# DOOM_SAO.net
KiCad netlist of a schematic drawn in EAGLE
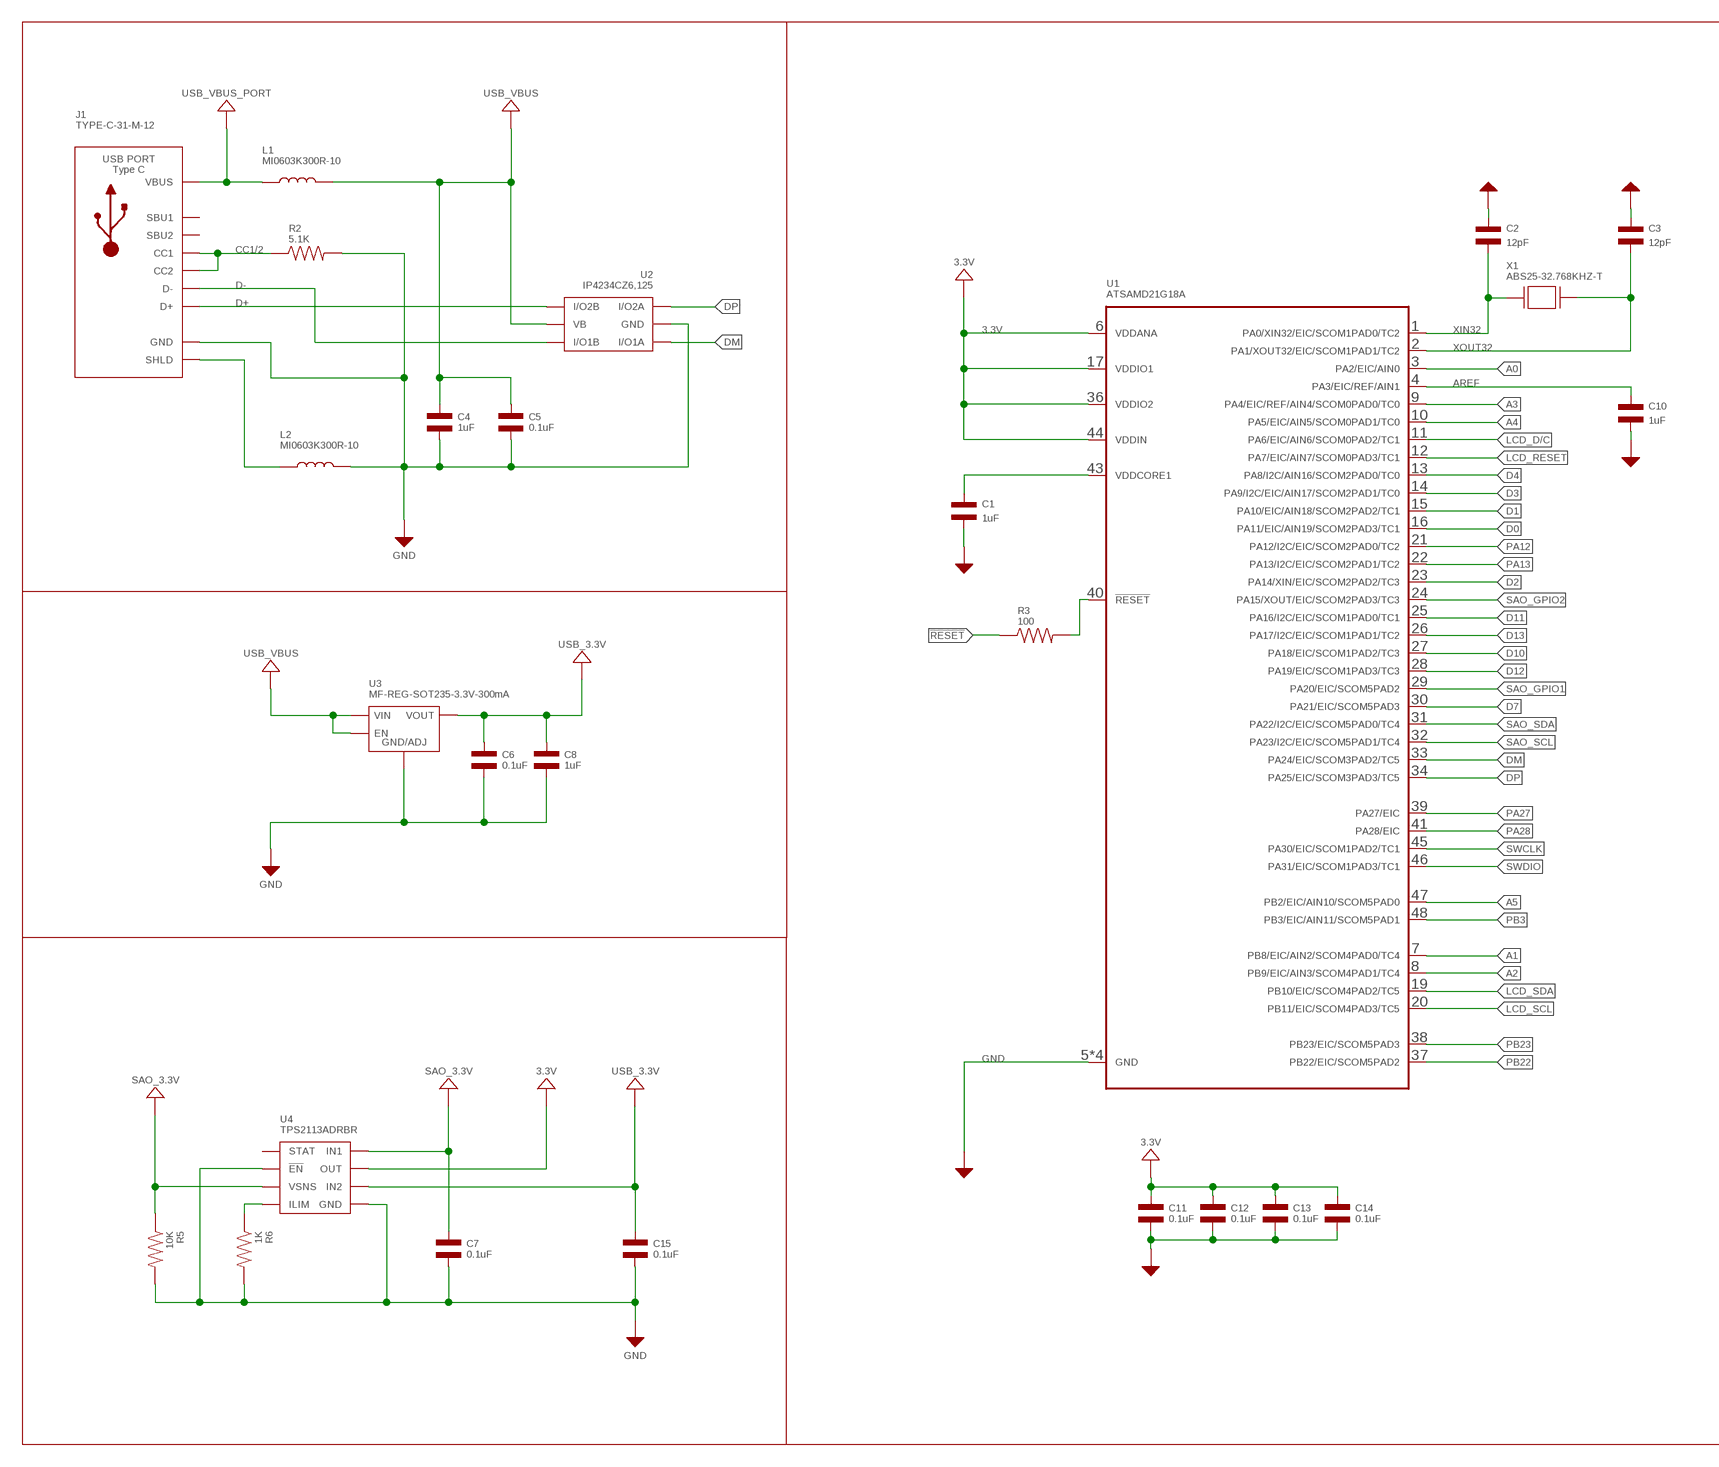
[diagram p0: schematic, sheet 1, part 1 of 2]
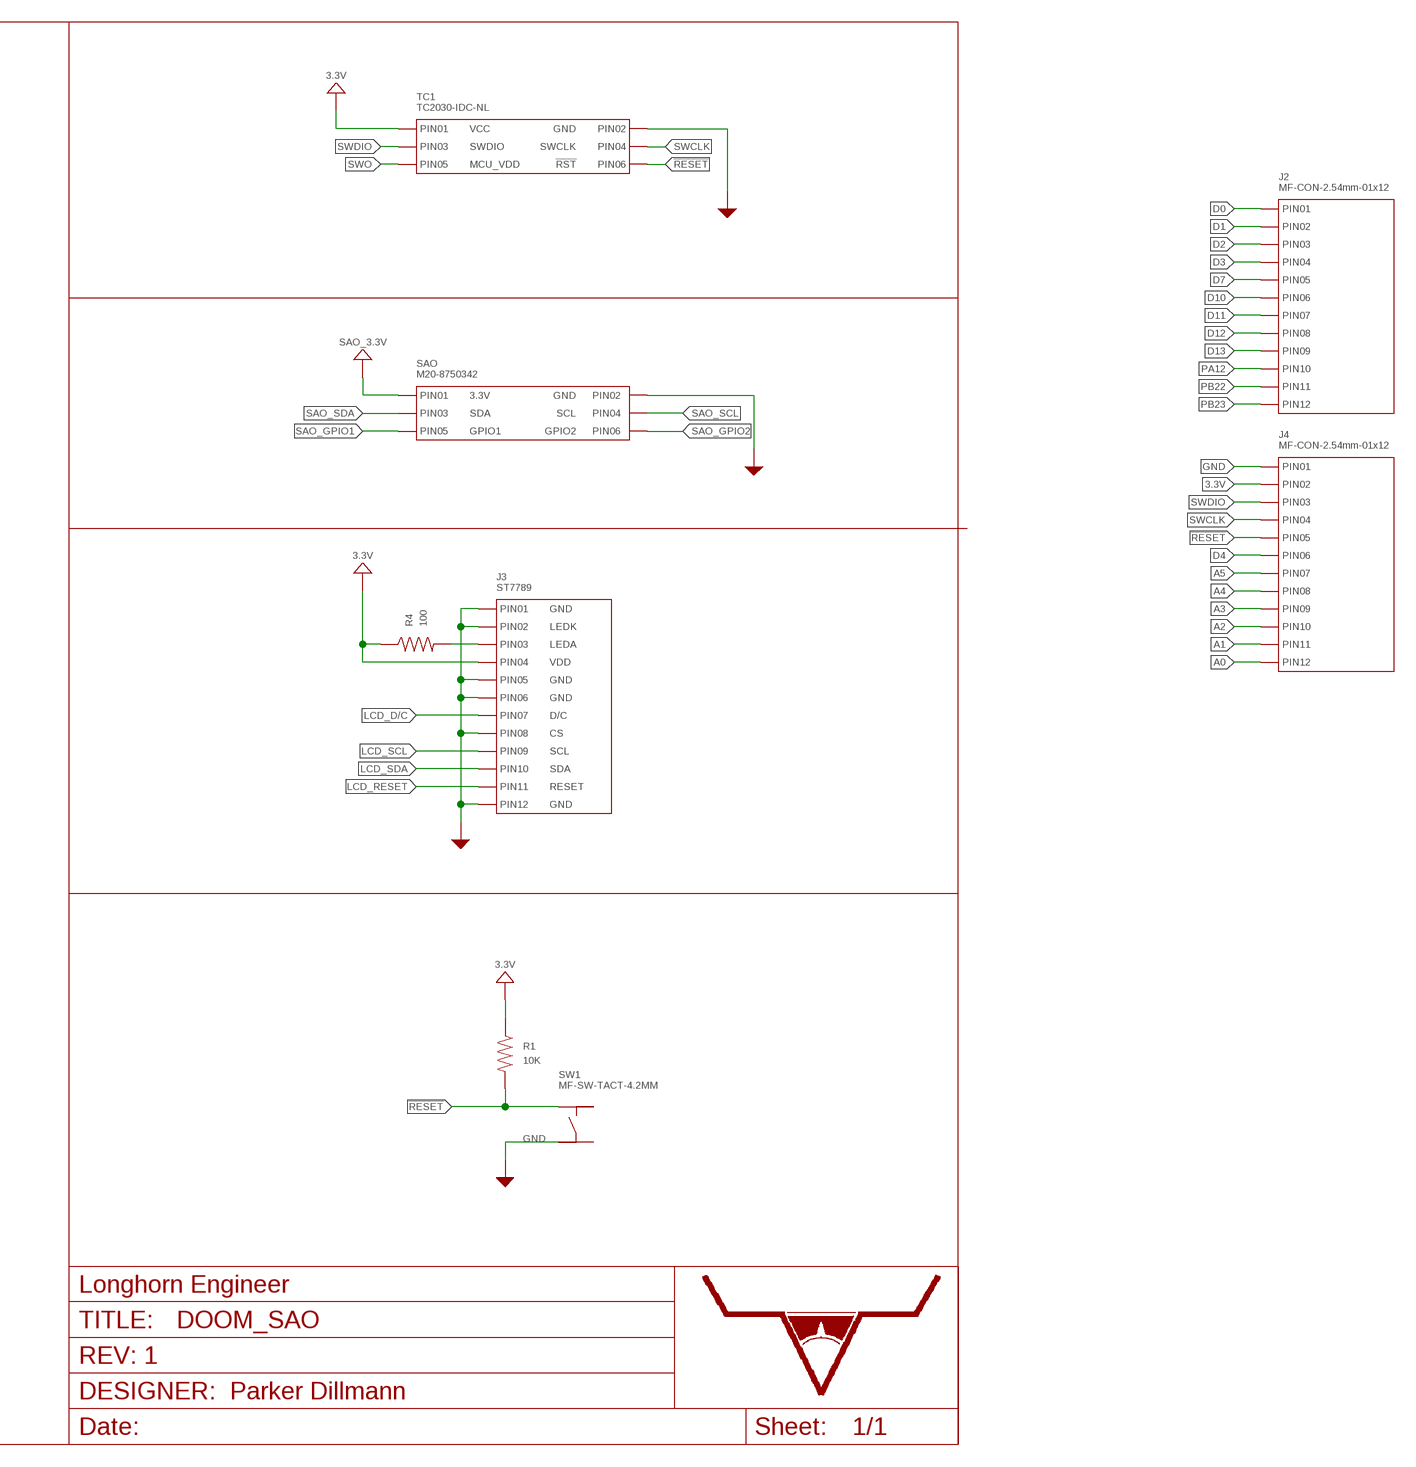
[diagram p1: schematic, sheet 1, part 2 of 2]

(export (version "E")
  (design (tool "Eeschema 10.0.6"))
  (components
    (comp (ref "C1")
      (value "1uF")
      (footprint "eagle-import:C0402")
      (fields (field (name "MPN") "MF-CAP-0402-1uF"))
      (libsource (lib "eagle-import") (part "CAPACITOR_NP_0402"))
    )
    (comp (ref "C2")
      (value "12pF")
      (footprint "eagle-import:C0402")
      (fields (field (name "MPN") "CC0402JRNPO9BN120"))
      (libsource (lib "eagle-import") (part "CAPACITOR_NP_0402"))
    )
    (comp (ref "C3")
      (value "12pF")
      (footprint "eagle-import:C0402")
      (fields (field (name "MPN") "CC0402JRNPO9BN120"))
      (libsource (lib "eagle-import") (part "CAPACITOR_NP_0402"))
    )
    (comp (ref "C4")
      (value "1uF")
      (footprint "eagle-import:C0402")
      (fields (field (name "MPN") "MF-CAP-0402-1uF"))
      (libsource (lib "eagle-import") (part "CAPACITOR_NP_0402"))
    )
    (comp (ref "C5")
      (value "0.1uF")
      (footprint "eagle-import:C0402")
      (fields (field (name "MPN") "MF-CAP-0402-0.1uF"))
      (libsource (lib "eagle-import") (part "CAPACITOR_NP_0402"))
    )
    (comp (ref "C6")
      (value "0.1uF")
      (footprint "eagle-import:C0402")
      (fields (field (name "MPN") "MF-CAP-0402-0.1uF"))
      (libsource (lib "eagle-import") (part "CAPACITOR_NP_0402"))
    )
    (comp (ref "C7")
      (value "0.1uF")
      (footprint "eagle-import:C0402")
      (fields (field (name "MPN") "MF-CAP-0402-0.1uF"))
      (libsource (lib "eagle-import") (part "CAPACITOR_NP_0402"))
    )
    (comp (ref "C8")
      (value "1uF")
      (footprint "eagle-import:C0402")
      (fields (field (name "MPN") "MF-CAP-0402-1uF"))
      (libsource (lib "eagle-import") (part "CAPACITOR_NP_0402"))
    )
    (comp (ref "C10")
      (value "1uF")
      (footprint "eagle-import:C0402")
      (fields (field (name "MPN") "MF-CAP-0402-1uF"))
      (libsource (lib "eagle-import") (part "CAPACITOR_NP_0402"))
    )
    (comp (ref "C11")
      (value "0.1uF")
      (footprint "eagle-import:C0402")
      (fields (field (name "MPN") "MF-CAP-0402-0.1uF"))
      (libsource (lib "eagle-import") (part "CAPACITOR_NP_0402"))
    )
    (comp (ref "C12")
      (value "0.1uF")
      (footprint "eagle-import:C0402")
      (fields (field (name "MPN") "MF-CAP-0402-0.1uF"))
      (libsource (lib "eagle-import") (part "CAPACITOR_NP_0402"))
    )
    (comp (ref "C13")
      (value "0.1uF")
      (footprint "eagle-import:C0402")
      (fields (field (name "MPN") "MF-CAP-0402-0.1uF"))
      (libsource (lib "eagle-import") (part "CAPACITOR_NP_0402"))
    )
    (comp (ref "C14")
      (value "0.1uF")
      (footprint "eagle-import:C0402")
      (fields (field (name "MPN") "MF-CAP-0402-0.1uF"))
      (libsource (lib "eagle-import") (part "CAPACITOR_NP_0402"))
    )
    (comp (ref "C15")
      (value "0.1uF")
      (footprint "eagle-import:C0402")
      (fields (field (name "MPN") "MF-CAP-0402-0.1uF"))
      (libsource (lib "eagle-import") (part "CAPACITOR_NP_0402"))
    )
    (comp (ref "J1")
      (value "TYPE-C-31-M-12")
      (footprint "eagle-import:TYPE-C-31-M-12")
      (libsource (lib "eagle-import") (part "USB_TYPE-C_MINIMAL"))
    )
    (comp (ref "J2")
      (value "MF-CON-2.54mm-01x12")
      (footprint "eagle-import:PTH_2.54MM_01X12")
      (fields (field (name "HOUSEPART") "YES"))
      (libsource (lib "eagle-import") (part "CON_01X12_PTH_2.54MM"))
    )
    (comp (ref "J3")
      (value "ST7789")
      (footprint "eagle-import:ST7789_CONNECTOR")
      (fields
        (field (name "LABEL01") "GND")
        (field (name "LABEL02") "LEDK")
        (field (name "LABEL03") "LEDA")
        (field (name "LABEL04") "VDD")
        (field (name "LABEL05") "GND")
        (field (name "LABEL06") "GND")
        (field (name "LABEL07") "D/C")
        (field (name "LABEL08") "CS")
        (field (name "LABEL09") "SCL")
        (field (name "LABEL10") "SDA")
        (field (name "LABEL11") "RESET")
        (field (name "LABEL12") "GND")
      )
      (libsource (lib "eagle-import") (part "CON_01X12_ST7789_CONNECTOR"))
    )
    (comp (ref "J4")
      (value "MF-CON-2.54mm-01x12")
      (footprint "eagle-import:PTH_2.54MM_01X12")
      (fields (field (name "HOUSEPART") "YES"))
      (libsource (lib "eagle-import") (part "CON_01X12_PTH_2.54MM"))
    )
    (comp (ref "L1")
      (value "MI0603K300R-10")
      (footprint "eagle-import:L0603")
      (fields (field (name "MPN") "MI0603K300R-10"))
      (libsource (lib "eagle-import") (part "INDUCTOR_0603"))
    )
    (comp (ref "L2")
      (value "MI0603K300R-10")
      (footprint "eagle-import:L0603")
      (fields (field (name "MPN") "MI0603K300R-10"))
      (libsource (lib "eagle-import") (part "INDUCTOR_0603"))
    )
    (comp (ref "R1")
      (value "10K")
      (footprint "eagle-import:R0402")
      (fields (field (name "MPN") "MF-RES-0402-10K"))
      (libsource (lib "eagle-import") (part "RESISTOR_0402"))
    )
    (comp (ref "R2")
      (value "5.1K")
      (footprint "eagle-import:R0402")
      (fields (field (name "MPN") "ERJ-2RHD5101X"))
      (libsource (lib "eagle-import") (part "RESISTOR_0402"))
    )
    (comp (ref "R3")
      (value "100")
      (footprint "eagle-import:R0402")
      (fields (field (name "MPN") "MF-RES-0402-100"))
      (libsource (lib "eagle-import") (part "RESISTOR_0402"))
    )
    (comp (ref "R4")
      (value "100")
      (footprint "eagle-import:R0402")
      (fields (field (name "MPN") "MF-RES-0402-100"))
      (libsource (lib "eagle-import") (part "RESISTOR_0402"))
    )
    (comp (ref "R5")
      (value "10K")
      (footprint "eagle-import:R0402")
      (fields (field (name "MPN") "MF-RES-0402-10K"))
      (libsource (lib "eagle-import") (part "RESISTOR_0402"))
    )
    (comp (ref "R6")
      (value "1K")
      (footprint "eagle-import:R0402")
      (fields (field (name "MPN") "MF-RES-0402-1K"))
      (libsource (lib "eagle-import") (part "RESISTOR_0402"))
    )
    (comp (ref "SAO")
      (value "M20-8750342")
      (footprint "eagle-import:M20-8750342")
      (fields
        (field (name "LABEL01") "3.3V")
        (field (name "LABEL02") "GND")
        (field (name "LABEL03") "SDA")
        (field (name "LABEL04") "SCL")
        (field (name "LABEL05") "GPIO1")
        (field (name "LABEL06") "GPIO2")
        (field (name "MPN") "M20-8750342 ")
        (field (name "POPULATE") "1")
      )
      (libsource (lib "eagle-import") (part "CON_02X03_M20-8750342"))
    )
    (comp (ref "SW1")
      (value "MF-SW-TACT-4.2MM")
      (footprint "eagle-import:TACT4.2MM")
      (fields (field (name "HOUSEPART") "YES"))
      (libsource (lib "eagle-import") (part "TACT_4.2MM"))
    )
    (comp (ref "TC1")
      (value "TC2030-IDC-NL")
      (footprint "eagle-import:TC2030-IDC-NL")
      (fields
        (field (name "HOUSEPART") "NO")
        (field (name "LABEL01") "VCC")
        (field (name "LABEL02") "GND")
        (field (name "LABEL03") "SWDIO")
        (field (name "LABEL04") "SWCLK")
        (field (name "LABEL05") "MCU_VDD")
        (field (name "LABEL06") "!RST")
      )
      (libsource (lib "eagle-import") (part "CON_02X03_TC2030-IDC-NL_SWD2TC"))
    )
    (comp (ref "U$8")
      (value "LHE_FRAME")
      (footprint "eagle-import:LHE_FRAME")
      (fields (field (name "DNAME") "Parker Dillmann") (field (name "REVNUM") "REV: 1"))
      (libsource (lib "eagle-import") (part "LHE_FRAME"))
    )
    (comp (ref "U1")
      (value "ATSAMD21G18A")
      (footprint "eagle-import:ATSAMD21G18A_TQFP-48")
      (fields (field (name "MPN") "ATSAMD21G18A-AU"))
      (libsource (lib "eagle-import") (part "ATSAMD21G18A-AU"))
    )
    (comp (ref "U2")
      (value "IP4234CZ6,125")
      (footprint "eagle-import:IP4234CZ6_SOT-457-6")
      (libsource (lib "eagle-import") (part "IP4234CZ6"))
    )
    (comp (ref "U3")
      (value "MF-REG-SOT235-3.3V-300mA")
      (footprint "eagle-import:SOT-23-5")
      (fields (field (name "HOUSEPART") "YES"))
      (libsource (lib "eagle-import") (part "TLV70233PDBVR"))
    )
    (comp (ref "U4")
      (value "TPS2113ADRBR")
      (footprint "eagle-import:TPS211X_SON-8")
      (libsource (lib "eagle-import") (part "TPS211(2/3)ADR"))
    )
    (comp (ref "X1")
      (value "ABS25-32.768KHZ-T")
      (footprint "eagle-import:ABS25_SERIES")
      (fields (field (name "HOUSEPART") "NO") (field (name "MPN") "ABS25-32.768KHZ-T "))
      (libsource (lib "eagle-import") (part "CYRSTAL_ABS25"))
    )
  )
  (nets
    (net (code "1") (name "/AREF") (class "Default")
      (node (ref "C10") (pin "P$1") (pinfunction "P$1_P$1") (pintype "passive"))
      (node (ref "U1") (pin "4") (pinfunction "PA3/EIC/REF/AIN1_4") (pintype "bidirectional"))
    )
    (net (code "2") (name "/CC1{slash}2") (class "Default")
      (node (ref "J1") (pin "A5") (pinfunction "CC1_A5") (pintype "bidirectional"))
      (node (ref "J1") (pin "B5") (pinfunction "CC2_B5") (pintype "bidirectional"))
      (node (ref "R2") (pin "P$1") (pinfunction "P$1_P$1") (pintype "passive"))
    )
    (net (code "3") (name "/D+") (class "Default")
      (node (ref "J1") (pin "A6") (pinfunction "D+_A6") (pintype "bidirectional"))
      (node (ref "J1") (pin "B6") (pinfunction "D+_B6") (pintype "bidirectional"))
      (node (ref "U2") (pin "4") (pinfunction "I/O2B_4") (pintype "bidirectional"))
    )
    (net (code "4") (name "/D-") (class "Default")
      (node (ref "J1") (pin "A7") (pinfunction "D-_A7") (pintype "bidirectional"))
      (node (ref "J1") (pin "B7") (pinfunction "D-_B7") (pintype "bidirectional"))
      (node (ref "U2") (pin "3") (pinfunction "I/O1B_3") (pintype "bidirectional"))
    )
    (net (code "5") (name "/XIN32") (class "Default")
      (node (ref "C2") (pin "P$2") (pinfunction "P$2_P$2") (pintype "passive"))
      (node (ref "U1") (pin "1") (pinfunction "PA0/XIN32/EIC/SCOM1PAD0/TC2_1") (pintype "bidirectional"))
      (node (ref "X1") (pin "1") (pinfunction "X0_1") (pintype "bidirectional"))
    )
    (net (code "6") (name "/XOUT32") (class "Default")
      (node (ref "C3") (pin "P$2") (pinfunction "P$2_P$2") (pintype "passive"))
      (node (ref "U1") (pin "2") (pinfunction "PA1/XOUT32/EIC/SCOM1PAD1/TC2_2") (pintype "bidirectional"))
      (node (ref "X1") (pin "4") (pinfunction "X1_4") (pintype "bidirectional"))
    )
    (net (code "7") (name "/~{RESET}") (class "Default")
      (node (ref "J4") (pin "P$5") (pinfunction "PIN5_P$5") (pintype "bidirectional"))
      (node (ref "R1") (pin "P$2") (pinfunction "P$2_P$2") (pintype "passive"))
      (node (ref "R3") (pin "P$1") (pinfunction "P$1_P$1") (pintype "passive"))
      (node (ref "SW1") (pin "P$1") (pinfunction "P$1_P$1") (pintype "bidirectional"))
      (node (ref "TC1") (pin "P$6") (pinfunction "PIN6_P$6") (pintype "bidirectional"))
    )
    (net (code "8") (name "3.3V") (class "Default")
      (node (ref "C11") (pin "P$1") (pinfunction "P$1_P$1") (pintype "passive"))
      (node (ref "C12") (pin "P$1") (pinfunction "P$1_P$1") (pintype "passive"))
      (node (ref "C13") (pin "P$1") (pinfunction "P$1_P$1") (pintype "passive"))
      (node (ref "C14") (pin "P$1") (pinfunction "P$1_P$1") (pintype "passive"))
      (node (ref "J3") (pin "P$4") (pinfunction "4_P$4") (pintype "bidirectional"))
      (node (ref "J4") (pin "P$2") (pinfunction "PIN2_P$2") (pintype "bidirectional"))
      (node (ref "R1") (pin "P$1") (pinfunction "P$1_P$1") (pintype "passive"))
      (node (ref "R4") (pin "P$1") (pinfunction "P$1_P$1") (pintype "passive"))
      (node (ref "TC1") (pin "P$1") (pinfunction "PIN1_P$1") (pintype "bidirectional"))
      (node (ref "U1") (pin "17") (pinfunction "VDDIO1_17") (pintype "bidirectional"))
      (node (ref "U1") (pin "36") (pinfunction "VDDIO2_36") (pintype "bidirectional"))
      (node (ref "U1") (pin "44") (pinfunction "VDDIN_44") (pintype "bidirectional"))
      (node (ref "U1") (pin "6") (pinfunction "VDDANA_6") (pintype "bidirectional"))
      (node (ref "U4") (pin "7") (pinfunction "OUT_7") (pintype "bidirectional"))
    )
    (net (code "9") (name "A0") (class "Default")
      (node (ref "J4") (pin "P$12") (pinfunction "PIN12_P$12") (pintype "bidirectional"))
      (node (ref "U1") (pin "3") (pinfunction "PA2/EIC/AIN0_3") (pintype "bidirectional"))
    )
    (net (code "10") (name "A1") (class "Default")
      (node (ref "J4") (pin "P$11") (pinfunction "PIN11_P$11") (pintype "bidirectional"))
      (node (ref "U1") (pin "7") (pinfunction "PB8/EIC/AIN2/SCOM4PAD0/TC4_7") (pintype "bidirectional"))
    )
    (net (code "11") (name "A2") (class "Default")
      (node (ref "J4") (pin "P$10") (pinfunction "PIN10_P$10") (pintype "bidirectional"))
      (node (ref "U1") (pin "8") (pinfunction "PB9/EIC/AIN3/SCOM4PAD1/TC4_8") (pintype "bidirectional"))
    )
    (net (code "12") (name "A3") (class "Default")
      (node (ref "J4") (pin "P$9") (pinfunction "PIN9_P$9") (pintype "bidirectional"))
      (node (ref "U1") (pin "9") (pinfunction "PA4/EIC/REF/AIN4/SCOM0PAD0/TC0_9") (pintype "bidirectional"))
    )
    (net (code "13") (name "A4") (class "Default")
      (node (ref "J4") (pin "P$8") (pinfunction "PIN8_P$8") (pintype "bidirectional"))
      (node (ref "U1") (pin "10") (pinfunction "PA5/EIC/AIN5/SCOM0PAD1/TC0_10") (pintype "bidirectional"))
    )
    (net (code "14") (name "A5") (class "Default")
      (node (ref "J4") (pin "P$7") (pinfunction "PIN7_P$7") (pintype "bidirectional"))
      (node (ref "U1") (pin "47") (pinfunction "PB2/EIC/AIN10/SCOM5PAD0_47") (pintype "bidirectional"))
    )
    (net (code "15") (name "D0") (class "Default")
      (node (ref "J2") (pin "P$1") (pinfunction "PIN1_P$1") (pintype "bidirectional"))
      (node (ref "U1") (pin "16") (pinfunction "PA11/EIC/AIN19/SCOM2PAD3/TC1_16") (pintype "bidirectional"))
    )
    (net (code "16") (name "D1") (class "Default")
      (node (ref "J2") (pin "P$2") (pinfunction "PIN2_P$2") (pintype "bidirectional"))
      (node (ref "U1") (pin "15") (pinfunction "PA10/EIC/AIN18/SCOM2PAD2/TC1_15") (pintype "bidirectional"))
    )
    (net (code "17") (name "D2") (class "Default")
      (node (ref "J2") (pin "P$3") (pinfunction "PIN3_P$3") (pintype "bidirectional"))
      (node (ref "U1") (pin "23") (pinfunction "PA14/XIN/EIC/SCOM2PAD2/TC3_23") (pintype "bidirectional"))
    )
    (net (code "18") (name "D3") (class "Default")
      (node (ref "J2") (pin "P$4") (pinfunction "PIN4_P$4") (pintype "bidirectional"))
      (node (ref "U1") (pin "14") (pinfunction "PA9/I2C/EIC/AIN17/SCOM2PAD1/TC0_14") (pintype "bidirectional"))
    )
    (net (code "19") (name "D4") (class "Default")
      (node (ref "J4") (pin "P$6") (pinfunction "PIN6_P$6") (pintype "bidirectional"))
      (node (ref "U1") (pin "13") (pinfunction "PA8/I2C/AIN16/SCOM2PAD0/TC0_13") (pintype "bidirectional"))
    )
    (net (code "20") (name "D7") (class "Default")
      (node (ref "J2") (pin "P$5") (pinfunction "PIN5_P$5") (pintype "bidirectional"))
      (node (ref "U1") (pin "30") (pinfunction "PA21/EIC/SCOM5PAD3_30") (pintype "bidirectional"))
    )
    (net (code "21") (name "D10") (class "Default")
      (node (ref "J2") (pin "P$6") (pinfunction "PIN6_P$6") (pintype "bidirectional"))
      (node (ref "U1") (pin "27") (pinfunction "PA18/EIC/SCOM1PAD2/TC3_27") (pintype "bidirectional"))
    )
    (net (code "22") (name "D11") (class "Default")
      (node (ref "J2") (pin "P$7") (pinfunction "PIN7_P$7") (pintype "bidirectional"))
      (node (ref "U1") (pin "25") (pinfunction "PA16/I2C/EIC/SCOM1PAD0/TC1_25") (pintype "bidirectional"))
    )
    (net (code "23") (name "D12") (class "Default")
      (node (ref "J2") (pin "P$8") (pinfunction "PIN8_P$8") (pintype "bidirectional"))
      (node (ref "U1") (pin "28") (pinfunction "PA19/EIC/SCOM1PAD3/TC3_28") (pintype "bidirectional"))
    )
    (net (code "24") (name "D13") (class "Default")
      (node (ref "J2") (pin "P$9") (pinfunction "PIN9_P$9") (pintype "bidirectional"))
      (node (ref "U1") (pin "26") (pinfunction "PA17/I2C/EIC/SCOM1PAD1/TC2_26") (pintype "bidirectional"))
    )
    (net (code "25") (name "DM") (class "Default")
      (node (ref "U1") (pin "33") (pinfunction "PA24/EIC/SCOM3PAD2/TC5_33") (pintype "bidirectional"))
      (node (ref "U2") (pin "1") (pinfunction "I/O1A_1") (pintype "bidirectional"))
    )
    (net (code "26") (name "DP") (class "Default")
      (node (ref "U1") (pin "34") (pinfunction "PA25/EIC/SCOM3PAD3/TC5_34") (pintype "bidirectional"))
      (node (ref "U2") (pin "6") (pinfunction "I/O2A_6") (pintype "bidirectional"))
    )
    (net (code "27") (name "GND") (class "Default")
      (node (ref "C1") (pin "P$2") (pinfunction "P$2_P$2") (pintype "passive"))
      (node (ref "C10") (pin "P$2") (pinfunction "P$2_P$2") (pintype "passive"))
      (node (ref "C11") (pin "P$2") (pinfunction "P$2_P$2") (pintype "passive"))
      (node (ref "C12") (pin "P$2") (pinfunction "P$2_P$2") (pintype "passive"))
      (node (ref "C13") (pin "P$2") (pinfunction "P$2_P$2") (pintype "passive"))
      (node (ref "C14") (pin "P$2") (pinfunction "P$2_P$2") (pintype "passive"))
      (node (ref "C15") (pin "P$2") (pinfunction "P$2_P$2") (pintype "passive"))
      (node (ref "C2") (pin "P$1") (pinfunction "P$1_P$1") (pintype "passive"))
      (node (ref "C3") (pin "P$1") (pinfunction "P$1_P$1") (pintype "passive"))
      (node (ref "C4") (pin "P$2") (pinfunction "P$2_P$2") (pintype "passive"))
      (node (ref "C5") (pin "P$2") (pinfunction "P$2_P$2") (pintype "passive"))
      (node (ref "C6") (pin "P$2") (pinfunction "P$2_P$2") (pintype "passive"))
      (node (ref "C7") (pin "P$2") (pinfunction "P$2_P$2") (pintype "passive"))
      (node (ref "C8") (pin "P$2") (pinfunction "P$2_P$2") (pintype "passive"))
      (node (ref "J1") (pin "A1/B12") (pinfunction "GND_A1/B12") (pintype "bidirectional"))
      (node (ref "J1") (pin "B1/A12") (pinfunction "GND_B1/A12") (pintype "bidirectional"))
      (node (ref "J3") (pin "P$1") (pinfunction "1_P$1") (pintype "bidirectional"))
      (node (ref "J3") (pin "P$12") (pinfunction "12_P$12") (pintype "bidirectional"))
      (node (ref "J3") (pin "P$2") (pinfunction "2_P$2") (pintype "bidirectional"))
      (node (ref "J3") (pin "P$5") (pinfunction "5_P$5") (pintype "bidirectional"))
      (node (ref "J3") (pin "P$6") (pinfunction "6_P$6") (pintype "bidirectional"))
      (node (ref "J3") (pin "P$8") (pinfunction "8_P$8") (pintype "bidirectional"))
      (node (ref "J4") (pin "P$1") (pinfunction "PIN1_P$1") (pintype "bidirectional"))
      (node (ref "L2") (pin "P$2") (pinfunction "P$2_P$2") (pintype "passive"))
      (node (ref "R2") (pin "P$2") (pinfunction "P$2_P$2") (pintype "passive"))
      (node (ref "R5") (pin "P$2") (pinfunction "P$2_P$2") (pintype "passive"))
      (node (ref "R6") (pin "P$2") (pinfunction "P$2_P$2") (pintype "passive"))
      (node (ref "SAO") (pin "2") (pinfunction "PIN2_2") (pintype "bidirectional"))
      (node (ref "SW1") (pin "P$3") (pinfunction "P$3_P$3") (pintype "bidirectional"))
      (node (ref "TC1") (pin "P$2") (pinfunction "PIN2_P$2") (pintype "bidirectional"))
      (node (ref "U1") (pin "18") (pinfunction "GND_18") (pintype "bidirectional"))
      (node (ref "U1") (pin "35") (pinfunction "GND_35") (pintype "bidirectional"))
      (node (ref "U1") (pin "42") (pinfunction "GND_42") (pintype "bidirectional"))
      (node (ref "U1") (pin "5") (pinfunction "GND_5") (pintype "bidirectional"))
      (node (ref "U2") (pin "2") (pinfunction "GND_2") (pintype "bidirectional"))
      (node (ref "U3") (pin "P$2") (pinfunction "GND/ADJ_P$2") (pintype "bidirectional"))
      (node (ref "U4") (pin "2") (pinfunction "~{EN}_2") (pintype "bidirectional"))
      (node (ref "U4") (pin "5") (pinfunction "GND_5") (pintype "bidirectional"))
      (node (ref "U4") (pin "PAD") (pinfunction "GND_PAD") (pintype "bidirectional"))
    )
    (net (code "28") (name "LCD_D{slash}C") (class "Default")
      (node (ref "J3") (pin "P$7") (pinfunction "7_P$7") (pintype "bidirectional"))
      (node (ref "U1") (pin "11") (pinfunction "PA6/EIC/AIN6/SCOM0PAD2/TC1_11") (pintype "bidirectional"))
    )
    (net (code "29") (name "LCD_RESET") (class "Default")
      (node (ref "J3") (pin "P$11") (pinfunction "11_P$11") (pintype "bidirectional"))
      (node (ref "U1") (pin "12") (pinfunction "PA7/EIC/AIN7/SCOM0PAD3/TC1_12") (pintype "bidirectional"))
    )
    (net (code "30") (name "LCD_SCL") (class "Default")
      (node (ref "J3") (pin "P$9") (pinfunction "9_P$9") (pintype "bidirectional"))
      (node (ref "U1") (pin "20") (pinfunction "PB11/EIC/SCOM4PAD3/TC5_20") (pintype "bidirectional"))
    )
    (net (code "31") (name "LCD_SDA") (class "Default")
      (node (ref "J3") (pin "P$10") (pinfunction "10_P$10") (pintype "bidirectional"))
      (node (ref "U1") (pin "19") (pinfunction "PB10/EIC/SCOM4PAD2/TC5_19") (pintype "bidirectional"))
    )
    (net (code "32") (name "Net-(J1-SHLD-PadMT_B_0)") (class "Default")
      (node (ref "J1") (pin "MT_B_0") (pinfunction "SHLD_MT_B_0") (pintype "bidirectional"))
      (node (ref "J1") (pin "MT_B_1") (pinfunction "SHLD_MT_B_1") (pintype "bidirectional"))
      (node (ref "J1") (pin "MT_B_2") (pinfunction "SHLD_MT_B_2") (pintype "bidirectional"))
      (node (ref "J1") (pin "MT_B_3") (pinfunction "SHLD_MT_B_3") (pintype "bidirectional"))
      (node (ref "J1") (pin "MT_T_0") (pinfunction "SHLD_MT_T_0") (pintype "bidirectional"))
      (node (ref "J1") (pin "MT_T_1") (pinfunction "SHLD_MT_T_1") (pintype "bidirectional"))
      (node (ref "J1") (pin "MT_T_2") (pinfunction "SHLD_MT_T_2") (pintype "bidirectional"))
      (node (ref "J1") (pin "MT_T_3") (pinfunction "SHLD_MT_T_3") (pintype "bidirectional"))
      (node (ref "L2") (pin "P$1") (pinfunction "P$1_P$1") (pintype "passive"))
    )
    (net (code "33") (name "Net-(J3-3)") (class "Default")
      (node (ref "J3") (pin "P$3") (pinfunction "3_P$3") (pintype "bidirectional"))
      (node (ref "R4") (pin "P$2") (pinfunction "P$2_P$2") (pintype "passive"))
    )
    (net (code "34") (name "Net-(U1-VDDCORE1)") (class "Default")
      (node (ref "C1") (pin "P$1") (pinfunction "P$1_P$1") (pintype "passive"))
      (node (ref "U1") (pin "43") (pinfunction "VDDCORE1_43") (pintype "bidirectional"))
    )
    (net (code "35") (name "Net-(U1-~{RESET})") (class "Default")
      (node (ref "R3") (pin "P$2") (pinfunction "P$2_P$2") (pintype "passive"))
      (node (ref "U1") (pin "40") (pinfunction "~{RESET}_40") (pintype "bidirectional"))
    )
    (net (code "36") (name "Net-(U4-ILIM)") (class "Default")
      (node (ref "R6") (pin "P$1") (pinfunction "P$1_P$1") (pintype "passive"))
      (node (ref "U4") (pin "4") (pinfunction "ILIM_4") (pintype "bidirectional"))
    )
    (net (code "37") (name "PA12") (class "Default")
      (node (ref "J2") (pin "P$10") (pinfunction "PIN10_P$10") (pintype "bidirectional"))
      (node (ref "U1") (pin "21") (pinfunction "PA12/I2C/EIC/SCOM2PAD0/TC2_21") (pintype "bidirectional"))
    )
    (net (code "38") (name "PA13") (class "Default")
      (node (ref "U1") (pin "22") (pinfunction "PA13/I2C/EIC/SCOM2PAD1/TC2_22") (pintype "bidirectional"))
    )
    (net (code "39") (name "PA27") (class "Default")
      (node (ref "U1") (pin "39") (pinfunction "PA27/EIC_39") (pintype "bidirectional"))
    )
    (net (code "40") (name "PA28") (class "Default")
      (node (ref "U1") (pin "41") (pinfunction "PA28/EIC_41") (pintype "bidirectional"))
    )
    (net (code "41") (name "PB3") (class "Default")
      (node (ref "U1") (pin "48") (pinfunction "PB3/EIC/AIN11/SCOM5PAD1_48") (pintype "bidirectional"))
    )
    (net (code "42") (name "PB22") (class "Default")
      (node (ref "J2") (pin "P$11") (pinfunction "PIN11_P$11") (pintype "bidirectional"))
      (node (ref "U1") (pin "37") (pinfunction "PB22/EIC/SCOM5PAD2_37") (pintype "bidirectional"))
    )
    (net (code "43") (name "PB23") (class "Default")
      (node (ref "J2") (pin "P$12") (pinfunction "PIN12_P$12") (pintype "bidirectional"))
      (node (ref "U1") (pin "38") (pinfunction "PB23/EIC/SCOM5PAD3_38") (pintype "bidirectional"))
    )
    (net (code "44") (name "SAO_3.3V") (class "Default")
      (node (ref "C7") (pin "P$1") (pinfunction "P$1_P$1") (pintype "passive"))
      (node (ref "R5") (pin "P$1") (pinfunction "P$1_P$1") (pintype "passive"))
      (node (ref "SAO") (pin "1") (pinfunction "PIN1_1") (pintype "bidirectional"))
      (node (ref "U4") (pin "3") (pinfunction "VSNS_3") (pintype "bidirectional"))
      (node (ref "U4") (pin "8") (pinfunction "IN1_8") (pintype "bidirectional"))
    )
    (net (code "45") (name "SAO_GPIO1") (class "Default")
      (node (ref "SAO") (pin "5") (pinfunction "PIN5_5") (pintype "bidirectional"))
      (node (ref "U1") (pin "29") (pinfunction "PA20/EIC/SCOM5PAD2_29") (pintype "bidirectional"))
    )
    (net (code "46") (name "SAO_GPIO2") (class "Default")
      (node (ref "SAO") (pin "6") (pinfunction "PIN6_6") (pintype "bidirectional"))
      (node (ref "U1") (pin "24") (pinfunction "PA15/XOUT/EIC/SCOM2PAD3/TC3_24") (pintype "bidirectional"))
    )
    (net (code "47") (name "SAO_SCL") (class "Default")
      (node (ref "SAO") (pin "4") (pinfunction "PIN4_4") (pintype "bidirectional"))
      (node (ref "U1") (pin "32") (pinfunction "PA23/I2C/EIC/SCOM5PAD1/TC4_32") (pintype "bidirectional"))
    )
    (net (code "48") (name "SAO_SDA") (class "Default")
      (node (ref "SAO") (pin "3") (pinfunction "PIN3_3") (pintype "bidirectional"))
      (node (ref "U1") (pin "31") (pinfunction "PA22/I2C/EIC/SCOM5PAD0/TC4_31") (pintype "bidirectional"))
    )
    (net (code "49") (name "SWCLK") (class "Default")
      (node (ref "J4") (pin "P$4") (pinfunction "PIN4_P$4") (pintype "bidirectional"))
      (node (ref "TC1") (pin "P$4") (pinfunction "PIN4_P$4") (pintype "bidirectional"))
      (node (ref "U1") (pin "45") (pinfunction "PA30/EIC/SCOM1PAD2/TC1_45") (pintype "bidirectional"))
    )
    (net (code "50") (name "SWDIO") (class "Default")
      (node (ref "J4") (pin "P$3") (pinfunction "PIN3_P$3") (pintype "bidirectional"))
      (node (ref "TC1") (pin "P$3") (pinfunction "PIN3_P$3") (pintype "bidirectional"))
      (node (ref "U1") (pin "46") (pinfunction "PA31/EIC/SCOM1PAD3/TC1_46") (pintype "bidirectional"))
    )
    (net (code "51") (name "SWO") (class "Default")
      (node (ref "TC1") (pin "P$5") (pinfunction "PIN5_P$5") (pintype "bidirectional"))
    )
    (net (code "52") (name "USB_3.3V") (class "Default")
      (node (ref "C15") (pin "P$1") (pinfunction "P$1_P$1") (pintype "passive"))
      (node (ref "C6") (pin "P$1") (pinfunction "P$1_P$1") (pintype "passive"))
      (node (ref "C8") (pin "P$1") (pinfunction "P$1_P$1") (pintype "passive"))
      (node (ref "U3") (pin "P$5") (pinfunction "VOUT_P$5") (pintype "bidirectional"))
      (node (ref "U4") (pin "6") (pinfunction "IN2_6") (pintype "bidirectional"))
    )
    (net (code "53") (name "USB_VBUS") (class "Default")
      (node (ref "C4") (pin "P$1") (pinfunction "P$1_P$1") (pintype "passive"))
      (node (ref "C5") (pin "P$1") (pinfunction "P$1_P$1") (pintype "passive"))
      (node (ref "L1") (pin "P$2") (pinfunction "P$2_P$2") (pintype "passive"))
      (node (ref "U2") (pin "5") (pinfunction "VB_5") (pintype "bidirectional"))
      (node (ref "U3") (pin "P$1") (pinfunction "VIN_P$1") (pintype "bidirectional"))
      (node (ref "U3") (pin "P$3") (pinfunction "EN_P$3") (pintype "bidirectional"))
    )
    (net (code "54") (name "USB_VBUS_PORT") (class "Default")
      (node (ref "J1") (pin "A4/B9") (pinfunction "VBUS_A4/B9") (pintype "bidirectional"))
      (node (ref "J1") (pin "B4/A9") (pinfunction "VBUS_B4/A9") (pintype "bidirectional"))
      (node (ref "L1") (pin "P$1") (pinfunction "P$1_P$1") (pintype "passive"))
    )
    (net (code "55") (name "unconnected-(J1-SBU1-PadA8)") (class "Default")
      (node (ref "J1") (pin "A8") (pinfunction "SBU1_A8") (pintype "bidirectional"))
    )
    (net (code "56") (name "unconnected-(J1-SBU2-PadB8)") (class "Default")
      (node (ref "J1") (pin "B8") (pinfunction "SBU2_B8") (pintype "bidirectional"))
    )
    (net (code "57") (name "unconnected-(SW1-PadP$2)") (class "Default")
      (node (ref "SW1") (pin "P$2") (pinfunction "P$2_P$2") (pintype "bidirectional"))
    )
    (net (code "58") (name "unconnected-(SW1-PadP$4)") (class "Default")
      (node (ref "SW1") (pin "P$4") (pinfunction "P$4_P$4") (pintype "bidirectional"))
    )
    (net (code "59") (name "unconnected-(U4-STAT-Pad1)") (class "Default")
      (node (ref "U4") (pin "1") (pinfunction "STAT_1") (pintype "bidirectional"))
    )
  )
)
